# Node_STM32.net
KiCad netlist of a schematic drawn in Altium Designer
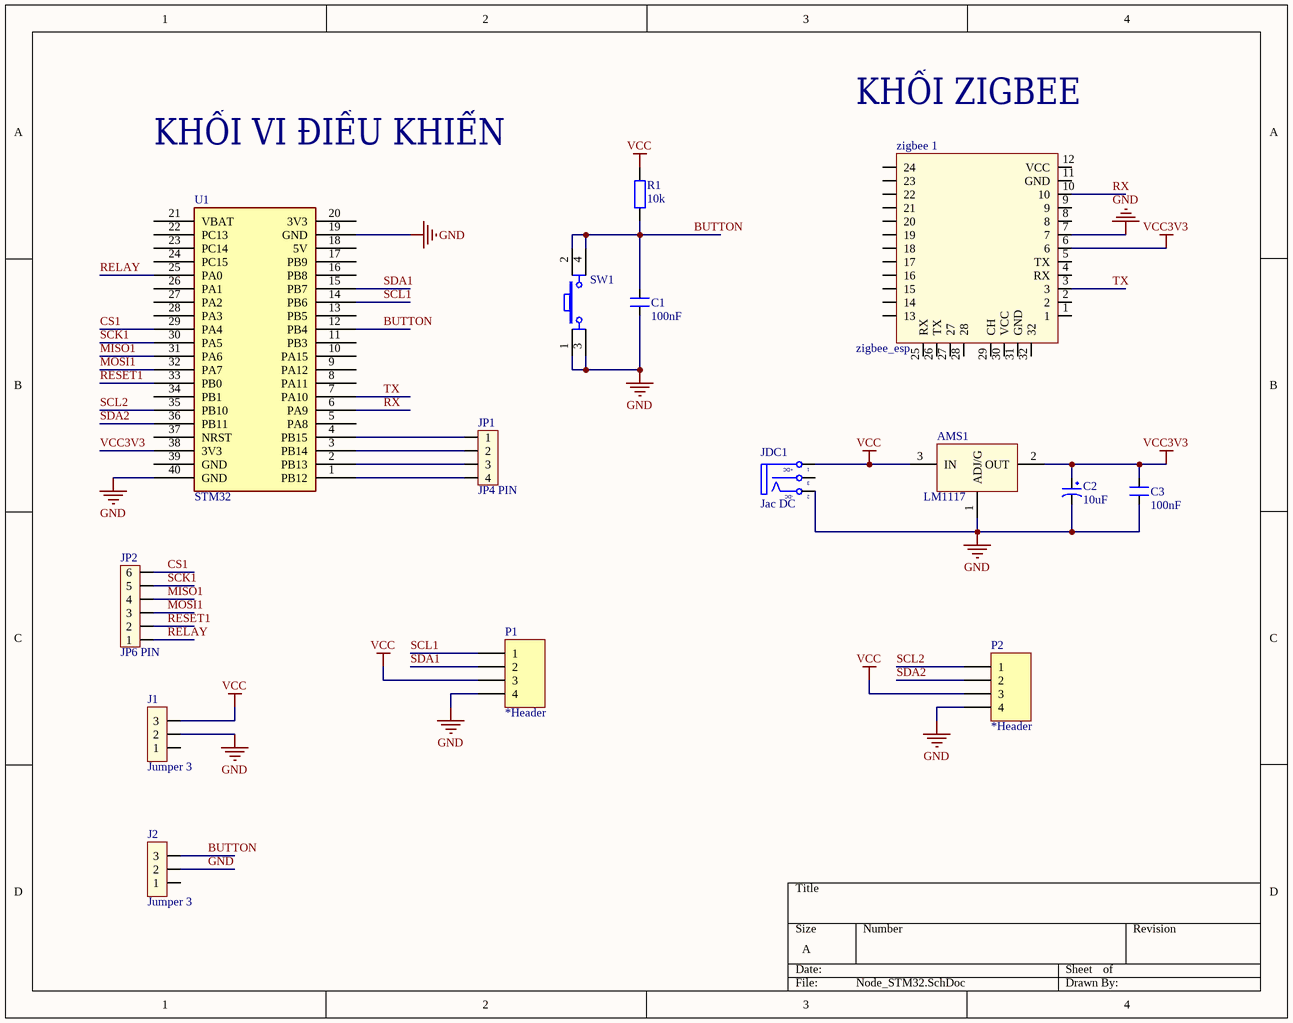
[diagram p0: Node_STM32.SchDoc]

(export (version "E")
  (design (tool "Eeschema 10.0.6"))
  (components
    (comp (ref "AMS1")
      (value "LM1117")
      (footprint "SOT223-4N")
      (description "Available in 1.8V, 2.5V, 2.85V, 3.3V, 5V, and  Adjustable Versions")
      (libsource (lib "ACtoDC") (part "LM1117"))
    )
    (comp (ref "C1")
      (value "100nF")
      (footprint "CN1")
      (description "Cremic For Xtal 1pF => 100pF")
      (libsource (lib "syhaunguyen") (part "CN0"))
    )
    (comp (ref "C2")
      (value "10uF")
      (footprint "CP1/2")
      (description "Cap P  0,1uF < 22uF , 16 - 50V")
      (libsource (lib "VioletofSun") (part "CP1"))
    )
    (comp (ref "C3")
      (value "100nF")
      (footprint "CN1")
      (description "Cremic For Xtal 1pF => 100pF")
      (libsource (lib "syhaunguyen") (part "CN0"))
    )
    (comp (ref "J1") (value "Jumper 3") (footprint "JP3") (libsource (lib "syhaunguyen") (part "JP3")))
    (comp (ref "J2") (value "Jumper 3") (footprint "JP3") (libsource (lib "syhaunguyen") (part "JP3")))
    (comp (ref "JDC1")
      (value "Jac DC")
      (footprint "DC-IN")
      (description "Jac DC input")
      (libsource (lib "syhaunguyen") (part "DCIN"))
    )
    (comp (ref "JP1") (value "JP4 PIN") (footprint "JP4") (libsource (lib "Cty1") (part "JP4")))
    (comp (ref "JP2") (value "JP6 PIN") (footprint "JP6") (libsource (lib "Cty1") (part "JP6")))
    (comp (ref "P1")
      (value "*Header")
      (footprint "HDR1X4")
      (description "Header, 4-Pin, Right Angle")
      (fields (field (name "PUBLISHER") "Altium Limited"))
      (libsource (lib "Cty1") (part "Header 4"))
    )
    (comp (ref "P2")
      (value "*Header")
      (footprint "HDR1X4")
      (description "Header, 4-Pin, Right Angle")
      (fields (field (name "PUBLISHER") "Altium Limited"))
      (libsource (lib "Cty1") (part "Header 4"))
    )
    (comp (ref "R1")
      (value "10k")
      (footprint "R1/4W")
      (description "Resistor 1/4W")
      (libsource (lib "syhaunguyen") (part "R1/4W"))
    )
    (comp (ref "SW1")
      (value "SW")
      (footprint "SW4")
      (description "Switch button 4 pin")
      (libsource (lib "syhaunguyen") (part "SW4"))
    )
    (comp (ref "U1")
      (value "STM32")
      (footprint "STM32")
      (libsource (lib "Other Microcontrollers") (part "STM32"))
    )
    (comp (ref "zigbee 1")
      (value "zigbee_esp")
      (footprint "zigbee")
      (libsource (lib "Main_stm8") (part "zigbee_esp"))
    )
  )
  (nets
    (net (code "2") (name "/BUTTON") (class "Default")
      (node (ref "C1") (pin "2") (pinfunction "2_2") (pintype "passive"))
      (node (ref "J2") (pin "3") (pinfunction "3_3") (pintype "passive"))
      (node (ref "R1") (pin "1") (pinfunction "1_1") (pintype "passive"))
      (node (ref "SW1") (pin "2") (pintype "passive"))
      (node (ref "SW1") (pin "4") (pintype "passive"))
      (node (ref "U1") (pin "12") (pinfunction "PB4_12") (pintype "passive"))
    )
    (net (code "3") (name "/CS1") (class "Default")
      (node (ref "JP2") (pin "6") (pinfunction "6_6") (pintype "passive"))
      (node (ref "U1") (pin "29") (pinfunction "PA4_29") (pintype "passive"))
    )
    (net (code "4") (name "/MISO1") (class "Default")
      (node (ref "JP2") (pin "4") (pinfunction "4_4") (pintype "passive"))
      (node (ref "U1") (pin "31") (pinfunction "PA6_31") (pintype "passive"))
    )
    (net (code "5") (name "/MOSI1") (class "Default")
      (node (ref "JP2") (pin "3") (pinfunction "3_3") (pintype "passive"))
      (node (ref "U1") (pin "32") (pinfunction "PA7_32") (pintype "passive"))
    )
    (net (code "6") (name "/RELAY") (class "Default")
      (node (ref "JP2") (pin "1") (pinfunction "1_1") (pintype "passive"))
      (node (ref "U1") (pin "25") (pinfunction "PA0_25") (pintype "passive"))
    )
    (net (code "7") (name "/RESET1") (class "Default")
      (node (ref "JP2") (pin "2") (pinfunction "2_2") (pintype "passive"))
      (node (ref "U1") (pin "33") (pinfunction "PB0_33") (pintype "passive"))
    )
    (net (code "8") (name "/RX") (class "Default")
      (node (ref "U1") (pin "6") (pinfunction "PA9_6") (pintype "passive"))
      (node (ref "zigbee 1") (pin "10") (pinfunction "10_10") (pintype "passive"))
    )
    (net (code "9") (name "/SCK1") (class "Default")
      (node (ref "JP2") (pin "5") (pinfunction "5_5") (pintype "passive"))
      (node (ref "U1") (pin "30") (pinfunction "PA5_30") (pintype "passive"))
    )
    (net (code "10") (name "/SCL1") (class "Default")
      (node (ref "P1") (pin "1") (pinfunction "1_1") (pintype "passive"))
      (node (ref "U1") (pin "14") (pinfunction "PB6_14") (pintype "passive"))
    )
    (net (code "11") (name "/SCL2") (class "Default")
      (node (ref "P2") (pin "1") (pinfunction "1_1") (pintype "passive"))
      (node (ref "U1") (pin "35") (pinfunction "PB10_35") (pintype "passive"))
    )
    (net (code "12") (name "/SDA1") (class "Default")
      (node (ref "P1") (pin "2") (pinfunction "2_2") (pintype "passive"))
      (node (ref "U1") (pin "15") (pinfunction "PB7_15") (pintype "passive"))
    )
    (net (code "13") (name "/SDA2") (class "Default")
      (node (ref "P2") (pin "2") (pinfunction "2_2") (pintype "passive"))
      (node (ref "U1") (pin "36") (pinfunction "PB11_36") (pintype "passive"))
    )
    (net (code "14") (name "/TX") (class "Default")
      (node (ref "U1") (pin "7") (pinfunction "PA10_7") (pintype "passive"))
      (node (ref "zigbee 1") (pin "3") (pinfunction "3_3") (pintype "passive"))
    )
    (net (code "15") (name "GND") (class "Default")
      (node (ref "AMS1") (pin "1") (pinfunction "ADJ/G_1") (pintype "passive"))
      (node (ref "C1") (pin "1") (pinfunction "1_1") (pintype "passive"))
      (node (ref "C2") (pin "2") (pinfunction "2_2") (pintype "passive"))
      (node (ref "C3") (pin "1") (pinfunction "1_1") (pintype "passive"))
      (node (ref "J1") (pin "2") (pinfunction "2_2") (pintype "passive"))
      (node (ref "J2") (pin "2") (pinfunction "2_2") (pintype "passive"))
      (node (ref "JDC1") (pin "2") (pinfunction "TN_2") (pintype "passive"))
      (node (ref "P1") (pin "4") (pinfunction "4_4") (pintype "passive"))
      (node (ref "P2") (pin "4") (pinfunction "4_4") (pintype "passive"))
      (node (ref "SW1") (pin "1") (pintype "passive"))
      (node (ref "SW1") (pin "3") (pintype "passive"))
      (node (ref "U1") (pin "19") (pinfunction "GND_19") (pintype "passive"))
      (node (ref "U1") (pin "40") (pinfunction "GND_40") (pintype "passive"))
      (node (ref "zigbee 1") (pin "7") (pinfunction "7_7") (pintype "passive"))
    )
    (net (code "16") (name "Net-(U1-PB12)") (class "Default")
      (node (ref "JP1") (pin "4") (pinfunction "4_4") (pintype "passive"))
      (node (ref "U1") (pin "1") (pinfunction "PB12_1") (pintype "passive"))
    )
    (net (code "17") (name "Net-(U1-PB13)") (class "Default")
      (node (ref "JP1") (pin "3") (pinfunction "3_3") (pintype "passive"))
      (node (ref "U1") (pin "2") (pinfunction "PB13_2") (pintype "passive"))
    )
    (net (code "18") (name "Net-(U1-PB14)") (class "Default")
      (node (ref "JP1") (pin "2") (pinfunction "2_2") (pintype "passive"))
      (node (ref "U1") (pin "3") (pinfunction "PB14_3") (pintype "passive"))
    )
    (net (code "19") (name "Net-(U1-PB15)") (class "Default")
      (node (ref "JP1") (pin "1") (pinfunction "1_1") (pintype "passive"))
      (node (ref "U1") (pin "4") (pinfunction "PB15_4") (pintype "passive"))
    )
    (net (code "20") (name "VCC") (class "Default")
      (node (ref "AMS1") (pin "3") (pinfunction "IN_3") (pintype "passive"))
      (node (ref "J1") (pin "3") (pinfunction "3_3") (pintype "passive"))
      (node (ref "JDC1") (pin "1") (pinfunction "T_1") (pintype "passive"))
      (node (ref "P1") (pin "3") (pinfunction "3_3") (pintype "passive"))
      (node (ref "P2") (pin "3") (pinfunction "3_3") (pintype "passive"))
      (node (ref "R1") (pin "2") (pinfunction "2_2") (pintype "passive"))
    )
    (net (code "21") (name "VCC3V3") (class "Default")
      (node (ref "AMS1") (pin "2") (pinfunction "OUT_2") (pintype "passive"))
      (node (ref "C2") (pin "1") (pinfunction "1_1") (pintype "passive"))
      (node (ref "C3") (pin "2") (pinfunction "2_2") (pintype "passive"))
      (node (ref "U1") (pin "38") (pinfunction "3V3_38") (pintype "passive"))
      (node (ref "zigbee 1") (pin "6") (pinfunction "6_6") (pintype "passive"))
    )
    (net (code "22") (name "unconnected-(J1-Pad1)") (class "Default")
      (node (ref "J1") (pin "1") (pinfunction "1_1") (pintype "passive"))
    )
    (net (code "23") (name "unconnected-(J2-Pad1)") (class "Default")
      (node (ref "J2") (pin "1") (pinfunction "1_1") (pintype "passive"))
    )
    (net (code "24") (name "unconnected-(JDC1-S-Pad3)") (class "Default")
      (node (ref "JDC1") (pin "3") (pinfunction "S_3") (pintype "power_in"))
    )
    (net (code "25") (name "unconnected-(U1-3V3-Pad20)") (class "Default")
      (node (ref "U1") (pin "20") (pinfunction "3V3_20") (pintype "passive"))
    )
    (net (code "26") (name "unconnected-(U1-5V-Pad18)") (class "Default")
      (node (ref "U1") (pin "18") (pinfunction "5V_18") (pintype "passive"))
    )
    (net (code "27") (name "unconnected-(U1-GND-Pad39)") (class "Default")
      (node (ref "U1") (pin "39") (pinfunction "GND_39") (pintype "passive"))
    )
    (net (code "28") (name "unconnected-(U1-NRST-Pad37)") (class "Default")
      (node (ref "U1") (pin "37") (pinfunction "NRST_37") (pintype "passive"))
    )
    (net (code "29") (name "unconnected-(U1-PA1-Pad26)") (class "Default")
      (node (ref "U1") (pin "26") (pinfunction "PA1_26") (pintype "passive"))
    )
    (net (code "30") (name "unconnected-(U1-PA2-Pad27)") (class "Default")
      (node (ref "U1") (pin "27") (pinfunction "PA2_27") (pintype "passive"))
    )
    (net (code "31") (name "unconnected-(U1-PA3-Pad28)") (class "Default")
      (node (ref "U1") (pin "28") (pinfunction "PA3_28") (pintype "passive"))
    )
    (net (code "32") (name "unconnected-(U1-PA8-Pad5)") (class "Default")
      (node (ref "U1") (pin "5") (pinfunction "PA8_5") (pintype "passive"))
    )
    (net (code "33") (name "unconnected-(U1-PA11-Pad8)") (class "Default")
      (node (ref "U1") (pin "8") (pinfunction "PA11_8") (pintype "passive"))
    )
    (net (code "34") (name "unconnected-(U1-PA12-Pad9)") (class "Default")
      (node (ref "U1") (pin "9") (pinfunction "PA12_9") (pintype "passive"))
    )
    (net (code "35") (name "unconnected-(U1-PA15-Pad10)") (class "Default")
      (node (ref "U1") (pin "10") (pinfunction "PA15_10") (pintype "passive"))
    )
    (net (code "36") (name "unconnected-(U1-PB1-Pad34)") (class "Default")
      (node (ref "U1") (pin "34") (pinfunction "PB1_34") (pintype "passive"))
    )
    (net (code "37") (name "unconnected-(U1-PB3-Pad11)") (class "Default")
      (node (ref "U1") (pin "11") (pinfunction "PB3_11") (pintype "passive"))
    )
    (net (code "38") (name "unconnected-(U1-PB5-Pad13)") (class "Default")
      (node (ref "U1") (pin "13") (pinfunction "PB5_13") (pintype "passive"))
    )
    (net (code "39") (name "unconnected-(U1-PB8-Pad16)") (class "Default")
      (node (ref "U1") (pin "16") (pinfunction "PB8_16") (pintype "passive"))
    )
    (net (code "40") (name "unconnected-(U1-PB9-Pad17)") (class "Default")
      (node (ref "U1") (pin "17") (pinfunction "PB9_17") (pintype "passive"))
    )
    (net (code "41") (name "unconnected-(U1-PC13-Pad22)") (class "Default")
      (node (ref "U1") (pin "22") (pinfunction "PC13_22") (pintype "passive"))
    )
    (net (code "42") (name "unconnected-(U1-PC14-Pad23)") (class "Default")
      (node (ref "U1") (pin "23") (pinfunction "PC14_23") (pintype "passive"))
    )
    (net (code "43") (name "unconnected-(U1-PC15-Pad24)") (class "Default")
      (node (ref "U1") (pin "24") (pinfunction "PC15_24") (pintype "passive"))
    )
    (net (code "44") (name "unconnected-(U1-VBAT-Pad21)") (class "Default")
      (node (ref "U1") (pin "21") (pinfunction "VBAT_21") (pintype "passive"))
    )
    (net (code "45") (name "unconnected-(zigbee 1-CH-Pad29)") (class "Default")
      (node (ref "zigbee 1") (pin "29") (pinfunction "CH_29") (pintype "passive"))
    )
    (net (code "46") (name "unconnected-(zigbee 1-GND-Pad11)") (class "Default")
      (node (ref "zigbee 1") (pin "11") (pinfunction "GND_11") (pintype "passive"))
    )
    (net (code "47") (name "unconnected-(zigbee 1-GND-Pad31)") (class "Default")
      (node (ref "zigbee 1") (pin "31") (pinfunction "GND_31") (pintype "passive"))
    )
    (net (code "48") (name "unconnected-(zigbee 1-Pad1)") (class "Default")
      (node (ref "zigbee 1") (pin "1") (pinfunction "1_1") (pintype "passive"))
    )
    (net (code "49") (name "unconnected-(zigbee 1-Pad2)") (class "Default")
      (node (ref "zigbee 1") (pin "2") (pinfunction "2_2") (pintype "passive"))
    )
    (net (code "50") (name "unconnected-(zigbee 1-Pad8)") (class "Default")
      (node (ref "zigbee 1") (pin "8") (pinfunction "8_8") (pintype "passive"))
    )
    (net (code "51") (name "unconnected-(zigbee 1-Pad9)") (class "Default")
      (node (ref "zigbee 1") (pin "9") (pinfunction "9_9") (pintype "passive"))
    )
    (net (code "52") (name "unconnected-(zigbee 1-Pad13)") (class "Default")
      (node (ref "zigbee 1") (pin "13") (pinfunction "13_13") (pintype "passive"))
    )
    (net (code "53") (name "unconnected-(zigbee 1-Pad14)") (class "Default")
      (node (ref "zigbee 1") (pin "14") (pinfunction "14_14") (pintype "passive"))
    )
    (net (code "54") (name "unconnected-(zigbee 1-Pad15)") (class "Default")
      (node (ref "zigbee 1") (pin "15") (pinfunction "15_15") (pintype "passive"))
    )
    (net (code "55") (name "unconnected-(zigbee 1-Pad16)") (class "Default")
      (node (ref "zigbee 1") (pin "16") (pinfunction "16_16") (pintype "passive"))
    )
    (net (code "56") (name "unconnected-(zigbee 1-Pad17)") (class "Default")
      (node (ref "zigbee 1") (pin "17") (pinfunction "17_17") (pintype "passive"))
    )
    (net (code "57") (name "unconnected-(zigbee 1-Pad18)") (class "Default")
      (node (ref "zigbee 1") (pin "18") (pinfunction "18_18") (pintype "passive"))
    )
    (net (code "58") (name "unconnected-(zigbee 1-Pad19)") (class "Default")
      (node (ref "zigbee 1") (pin "19") (pinfunction "19_19") (pintype "passive"))
    )
    (net (code "59") (name "unconnected-(zigbee 1-Pad20)") (class "Default")
      (node (ref "zigbee 1") (pin "20") (pinfunction "20_20") (pintype "passive"))
    )
    (net (code "60") (name "unconnected-(zigbee 1-Pad21)") (class "Default")
      (node (ref "zigbee 1") (pin "21") (pinfunction "21_21") (pintype "passive"))
    )
    (net (code "61") (name "unconnected-(zigbee 1-Pad22)") (class "Default")
      (node (ref "zigbee 1") (pin "22") (pinfunction "22_22") (pintype "passive"))
    )
    (net (code "62") (name "unconnected-(zigbee 1-Pad23)") (class "Default")
      (node (ref "zigbee 1") (pin "23") (pinfunction "23_23") (pintype "passive"))
    )
    (net (code "63") (name "unconnected-(zigbee 1-Pad24)") (class "Default")
      (node (ref "zigbee 1") (pin "24") (pinfunction "24_24") (pintype "passive"))
    )
    (net (code "64") (name "unconnected-(zigbee 1-Pad27)") (class "Default")
      (node (ref "zigbee 1") (pin "27") (pinfunction "27_27") (pintype "passive"))
    )
    (net (code "65") (name "unconnected-(zigbee 1-Pad28)") (class "Default")
      (node (ref "zigbee 1") (pin "28") (pinfunction "28_28") (pintype "passive"))
    )
    (net (code "66") (name "unconnected-(zigbee 1-Pad32)") (class "Default")
      (node (ref "zigbee 1") (pin "32") (pinfunction "32_32") (pintype "passive"))
    )
    (net (code "67") (name "unconnected-(zigbee 1-RX-Pad4)") (class "Default")
      (node (ref "zigbee 1") (pin "4") (pinfunction "RX_4") (pintype "passive"))
    )
    (net (code "68") (name "unconnected-(zigbee 1-RX-Pad25)") (class "Default")
      (node (ref "zigbee 1") (pin "25") (pinfunction "RX_25") (pintype "passive"))
    )
    (net (code "69") (name "unconnected-(zigbee 1-TX-Pad5)") (class "Default")
      (node (ref "zigbee 1") (pin "5") (pinfunction "TX_5") (pintype "passive"))
    )
    (net (code "70") (name "unconnected-(zigbee 1-TX-Pad26)") (class "Default")
      (node (ref "zigbee 1") (pin "26") (pinfunction "TX_26") (pintype "passive"))
    )
    (net (code "71") (name "unconnected-(zigbee 1-VCC-Pad12)") (class "Default")
      (node (ref "zigbee 1") (pin "12") (pinfunction "VCC_12") (pintype "passive"))
    )
    (net (code "72") (name "unconnected-(zigbee 1-VCC-Pad30)") (class "Default")
      (node (ref "zigbee 1") (pin "30") (pinfunction "VCC_30") (pintype "passive"))
    )
  )
)
